# 11_Clock_1.net
KiCad netlist of a schematic drawn in Altium Designer
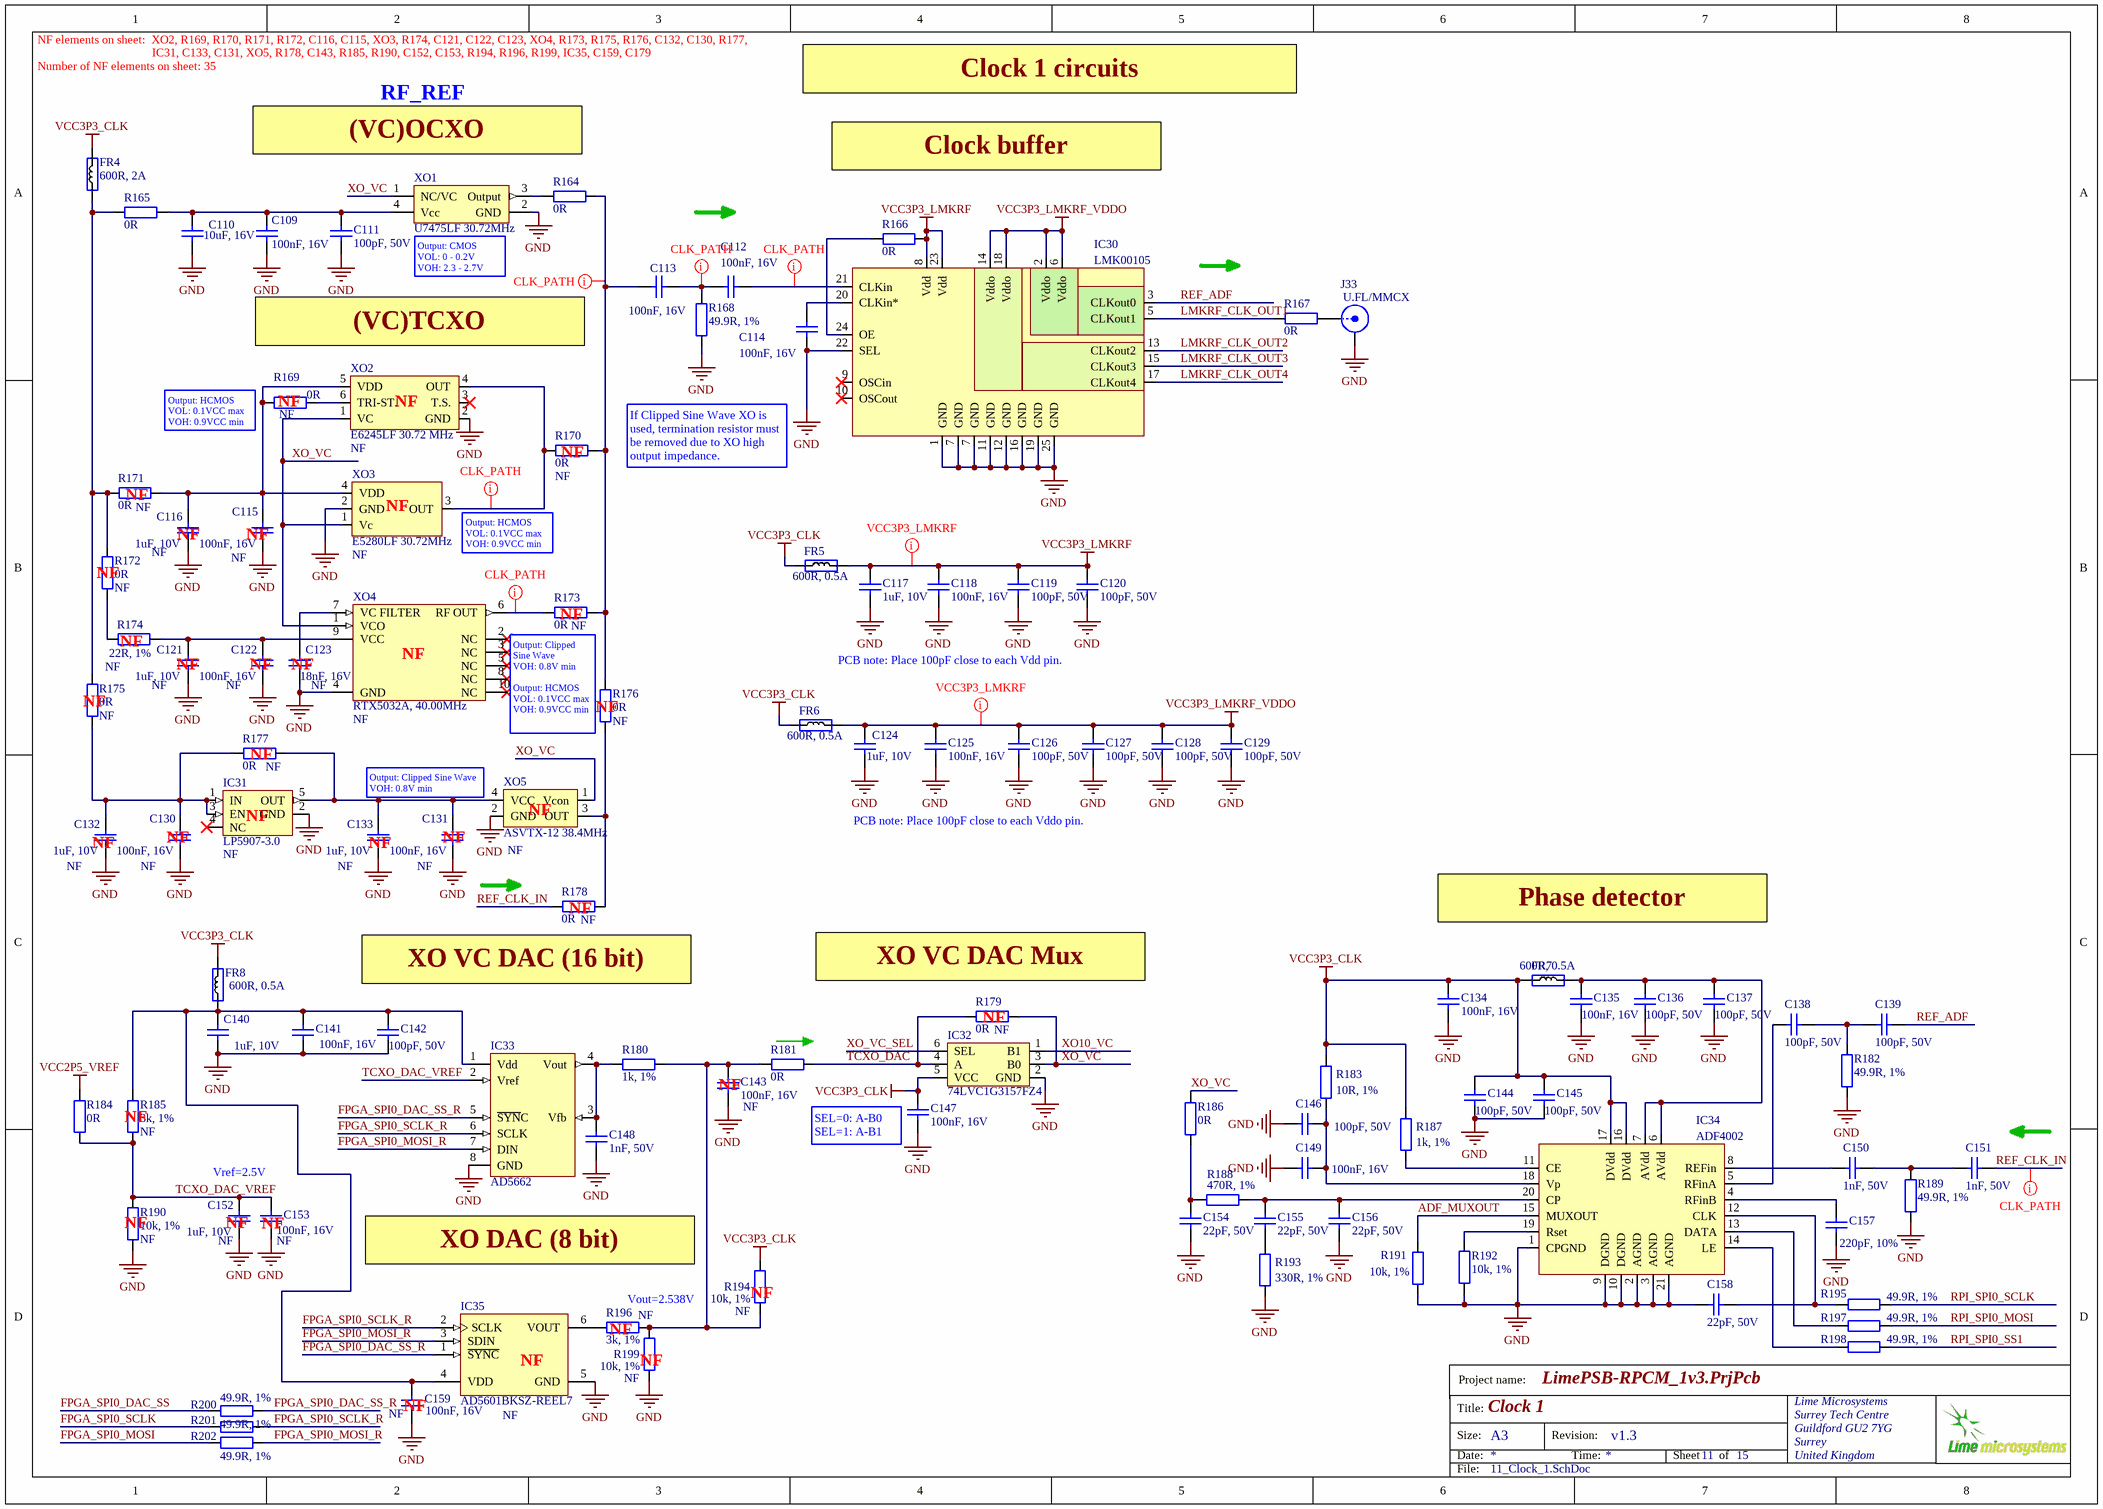
[diagram p0: 11_Clock_1.SchDoc]

(export (version "E")
  (design (tool "Eeschema 10.0.6"))
  (components
    (comp (ref "C109")
      (value "100nF, 16V")
      (footprint "CAP0402")
      (fields
        (field (name "MANUFACTURER") "Murata Electronics")
        (field (name "TOLERANCE") "10 %")
        (field (name "MANUFACTURER PART NUMBER") "GRM155R71C104KA88D")
      )
      (libsource (lib "LimeMicroAltiumLib_schLib") (part "Cap_0402"))
    )
    (comp (ref "C110")
      (value "10uF, 16V")
      (footprint "CAP0603")
      (fields (field (name "MANUFACTURER") "Yageo") (field (name "TOLERANCE") "±20%"))
      (libsource (lib "LimeMicroAltiumLib_schLib") (part "Cap_0603"))
    )
    (comp (ref "C111")
      (value "100pF, 50V")
      (footprint "CAP0402")
      (fields (field (name "TOLERANCE") "±5%") (field (name "MANUFACTURER") "Yageo"))
      (libsource (lib "LimeMicroAltiumLib_schLib") (part "Cap_0402"))
    )
    (comp (ref "C112")
      (value "100nF, 16V")
      (footprint "CAP0402")
      (fields
        (field (name "MANUFACTURER") "Murata Electronics")
        (field (name "TOLERANCE") "10 %")
        (field (name "MANUFACTURER PART NUMBER") "GRM155R71C104KA88D")
      )
      (libsource (lib "LimeMicroAltiumLib_schLib") (part "Cap_0402"))
    )
    (comp (ref "C113")
      (value "100nF, 16V")
      (footprint "CAP0402")
      (fields
        (field (name "MANUFACTURER") "Murata Electronics")
        (field (name "TOLERANCE") "10 %")
        (field (name "MANUFACTURER PART NUMBER") "GRM155R71C104KA88D")
      )
      (libsource (lib "LimeMicroAltiumLib_schLib") (part "Cap_0402"))
    )
    (comp (ref "C114")
      (value "100nF, 16V")
      (footprint "CAP0402")
      (fields
        (field (name "MANUFACTURER") "Murata Electronics")
        (field (name "TOLERANCE") "10 %")
        (field (name "MANUFACTURER PART NUMBER") "GRM155R71C104KA88D")
      )
      (libsource (lib "LimeMicroAltiumLib_schLib") (part "Cap_0402"))
    )
    (comp (ref "C115")
      (value "100nF, 16V")
      (footprint "CAP0402")
      (fields
        (field (name "ASSEMBLY INFO") "NF")
        (field (name "MANUFACTURER") "Murata Electronics")
        (field (name "TOLERANCE") "10 %")
        (field (name "MANUFACTURER PART NUMBER") "GRM155R71C104KA88D")
      )
      (libsource (lib "LimeMicroAltiumLib_schLib") (part "Cap_0402"))
    )
    (comp (ref "C116")
      (value "1uF, 10V")
      (footprint "CAP0402")
      (description "CAP CER 1UF 10V X5R 0402")
      (fields (field (name "ASSEMBLY INFO") "NF") (field (name "MANUFACTURER") "Yageo"))
      (libsource (lib "LimeMicroAltiumLib_schLib") (part "Cap_0402"))
    )
    (comp (ref "C117")
      (value "1uF, 10V")
      (footprint "CAP0402")
      (description "CAP CER 1UF 10V X5R 0402")
      (fields (field (name "MANUFACTURER") "Yageo") (field (name "TOLERANCE") "±20%"))
      (libsource (lib "LimeMicroAltiumLib_schLib") (part "Cap_0402"))
    )
    (comp (ref "C118")
      (value "100nF, 16V")
      (footprint "CAP0402")
      (fields
        (field (name "MANUFACTURER") "Murata Electronics")
        (field (name "TOLERANCE") "10 %")
        (field (name "MANUFACTURER PART NUMBER") "GRM155R71C104KA88D")
      )
      (libsource (lib "LimeMicroAltiumLib_schLib") (part "Cap_0402"))
    )
    (comp (ref "C119")
      (value "100pF, 50V")
      (footprint "CAP0402")
      (fields (field (name "MANUFACTURER") "Yageo") (field (name "TOLERANCE") "±5%"))
      (libsource (lib "LimeMicroAltiumLib_schLib") (part "Cap_0402"))
    )
    (comp (ref "C120")
      (value "100pF, 50V")
      (footprint "CAP0402")
      (fields (field (name "MANUFACTURER") "Yageo") (field (name "TOLERANCE") "±5%"))
      (libsource (lib "LimeMicroAltiumLib_schLib") (part "Cap_0402"))
    )
    (comp (ref "C121")
      (value "1uF, 10V")
      (footprint "CAP0402")
      (description "CAP CER 1UF 10V X5R 0402")
      (fields (field (name "ASSEMBLY INFO") "NF") (field (name "MANUFACTURER") "Yageo"))
      (libsource (lib "LimeMicroAltiumLib_schLib") (part "Cap_0402"))
    )
    (comp (ref "C122")
      (value "100nF, 16V")
      (footprint "CAP0402")
      (fields
        (field (name "ASSEMBLY INFO") "NF")
        (field (name "MANUFACTURER") "Murata Electronics")
        (field (name "TOLERANCE") "10 %")
        (field (name "MANUFACTURER PART NUMBER") "GRM155R71C104KA88D")
      )
      (libsource (lib "LimeMicroAltiumLib_schLib") (part "Cap_0402"))
    )
    (comp (ref "C123")
      (value "18nF, 16V")
      (footprint "CAP0402")
      (fields
        (field (name "ASSEMBLY INFO") "NF")
        (field (name "MANUFACTURER") "Yageo")
        (field (name "TOLERANCE") "±10%")
      )
      (libsource (lib "LimeMicroAltiumLib_schLib") (part "Cap_0402"))
    )
    (comp (ref "C124")
      (value "1uF, 10V")
      (footprint "CAP0402")
      (description "CAP CER 1UF 10V X5R 0402")
      (fields (field (name "MANUFACTURER") "Yageo") (field (name "TOLERANCE") "±20%"))
      (libsource (lib "LimeMicroAltiumLib_schLib") (part "Cap_0402"))
    )
    (comp (ref "C125")
      (value "100nF, 16V")
      (footprint "CAP0402")
      (fields
        (field (name "MANUFACTURER") "Murata Electronics")
        (field (name "TOLERANCE") "10 %")
        (field (name "MANUFACTURER PART NUMBER") "GRM155R71C104KA88D")
      )
      (libsource (lib "LimeMicroAltiumLib_schLib") (part "Cap_0402"))
    )
    (comp (ref "C126")
      (value "100pF, 50V")
      (footprint "CAP0402")
      (fields (field (name "MANUFACTURER") "Yageo") (field (name "TOLERANCE") "±5%"))
      (libsource (lib "LimeMicroAltiumLib_schLib") (part "Cap_0402"))
    )
    (comp (ref "C127")
      (value "100pF, 50V")
      (footprint "CAP0402")
      (fields (field (name "MANUFACTURER") "Yageo") (field (name "TOLERANCE") "±5%"))
      (libsource (lib "LimeMicroAltiumLib_schLib") (part "Cap_0402"))
    )
    (comp (ref "C128")
      (value "100pF, 50V")
      (footprint "CAP0402")
      (fields (field (name "MANUFACTURER") "Yageo") (field (name "TOLERANCE") "±5%"))
      (libsource (lib "LimeMicroAltiumLib_schLib") (part "Cap_0402"))
    )
    (comp (ref "C129")
      (value "100pF, 50V")
      (footprint "CAP0402")
      (fields (field (name "MANUFACTURER") "Yageo") (field (name "TOLERANCE") "±5%"))
      (libsource (lib "LimeMicroAltiumLib_schLib") (part "Cap_0402"))
    )
    (comp (ref "C130")
      (value "100nF, 16V")
      (footprint "CAP0402")
      (fields
        (field (name "ASSEMBLY INFO") "NF")
        (field (name "MANUFACTURER") "Murata Electronics")
        (field (name "TOLERANCE") "10 %")
        (field (name "MANUFACTURER PART NUMBER") "GRM155R71C104KA88D")
      )
      (libsource (lib "") (part "Cap_0402_1"))
    )
    (comp (ref "C131")
      (value "100nF, 16V")
      (footprint "CAP0402")
      (fields
        (field (name "ASSEMBLY INFO") "NF")
        (field (name "MANUFACTURER") "Murata Electronics")
        (field (name "TOLERANCE") "10 %")
        (field (name "MANUFACTURER PART NUMBER") "GRM155R71C104KA88D")
      )
      (libsource (lib "") (part "Cap_0402_1"))
    )
    (comp (ref "C132")
      (value "1uF, 10V")
      (footprint "CAP0402")
      (fields (field (name "ASSEMBLY INFO") "NF") (field (name "MANUFACTURER") "Yageo"))
      (libsource (lib "") (part "Cap_0402_1"))
    )
    (comp (ref "C133")
      (value "1uF, 10V")
      (footprint "CAP0402")
      (fields (field (name "ASSEMBLY INFO") "NF") (field (name "MANUFACTURER") "Yageo"))
      (libsource (lib "") (part "Cap_0402_1"))
    )
    (comp (ref "C134")
      (value "100nF, 16V")
      (footprint "CAP0402")
      (fields
        (field (name "MANUFACTURER") "Murata Electronics")
        (field (name "TOLERANCE") "10 %")
        (field (name "MANUFACTURER PART NUMBER") "GRM155R71C104KA88D")
      )
      (libsource (lib "LimeMicroAltiumLib_schLib") (part "Cap_0402"))
    )
    (comp (ref "C135")
      (value "100nF, 16V")
      (footprint "CAP0402")
      (fields
        (field (name "MANUFACTURER") "Murata Electronics")
        (field (name "TOLERANCE") "10 %")
        (field (name "MANUFACTURER PART NUMBER") "GRM155R71C104KA88D")
      )
      (libsource (lib "LimeMicroAltiumLib_schLib") (part "Cap_0402"))
    )
    (comp (ref "C136")
      (value "100pF, 50V")
      (footprint "CAP0402")
      (fields (field (name "MANUFACTURER") "Yageo") (field (name "TOLERANCE") "±5%"))
      (libsource (lib "LimeMicroAltiumLib_schLib") (part "Cap_0402"))
    )
    (comp (ref "C137")
      (value "100pF, 50V")
      (footprint "CAP0402")
      (fields (field (name "MANUFACTURER") "Yageo") (field (name "TOLERANCE") "±5%"))
      (libsource (lib "LimeMicroAltiumLib_schLib") (part "Cap_0402"))
    )
    (comp (ref "C138")
      (value "100pF, 50V")
      (footprint "CAP0402")
      (fields (field (name "MANUFACTURER") "Yageo") (field (name "TOLERANCE") "±5%"))
      (libsource (lib "LimeMicroAltiumLib_schLib") (part "Cap_0402"))
    )
    (comp (ref "C139")
      (value "100pF, 50V")
      (footprint "CAP0402")
      (fields (field (name "MANUFACTURER") "Yageo") (field (name "TOLERANCE") "±5%"))
      (libsource (lib "LimeMicroAltiumLib_schLib") (part "Cap_0402"))
    )
    (comp (ref "C140")
      (value "1uF, 10V")
      (footprint "CAP0402")
      (description "CAP CER 1UF 10V X5R 0402")
      (fields (field (name "MANUFACTURER") "Yageo") (field (name "TOLERANCE") "±20%"))
      (libsource (lib "LimeMicroAltiumLib_schLib") (part "Cap_0402"))
    )
    (comp (ref "C141")
      (value "100nF, 16V")
      (footprint "CAP0402")
      (fields
        (field (name "TOLERANCE") "10 %")
        (field (name "MANUFACTURER") "Murata Electronics")
        (field (name "MANUFACTURER PART NUMBER") "GRM155R71C104KA88D")
      )
      (libsource (lib "LimeFPGAboard_schLib") (part "Cap_0603"))
    )
    (comp (ref "C142")
      (value "100pF, 50V")
      (footprint "CAP0402")
      (fields (field (name "MANUFACTURER") "Yageo") (field (name "TOLERANCE") "±5%"))
      (libsource (lib "LimeMicroAltiumLib_schLib") (part "Cap_0402"))
    )
    (comp (ref "C143")
      (value "100nF, 16V")
      (footprint "CAP0402")
      (fields
        (field (name "ASSEMBLY INFO") "NF")
        (field (name "MANUFACTURER") "Murata Electronics")
        (field (name "TOLERANCE") "10 %")
        (field (name "MANUFACTURER PART NUMBER") "GRM155R71C104KA88D")
      )
      (libsource (lib "LimeMicroAltiumLib_schLib") (part "Cap_0402"))
    )
    (comp (ref "C144")
      (value "100pF, 50V")
      (footprint "CAP0402")
      (fields (field (name "MANUFACTURER") "Yageo") (field (name "TOLERANCE") "±5%"))
      (libsource (lib "LimeMicroAltiumLib_schLib") (part "Cap_0402"))
    )
    (comp (ref "C145")
      (value "100pF, 50V")
      (footprint "CAP0402")
      (fields (field (name "MANUFACTURER") "Yageo") (field (name "TOLERANCE") "±5%"))
      (libsource (lib "LimeMicroAltiumLib_schLib") (part "Cap_0402"))
    )
    (comp (ref "C146")
      (value "100pF, 50V")
      (footprint "CAP0402")
      (fields (field (name "MANUFACTURER") "Yageo") (field (name "TOLERANCE") "±5%"))
      (libsource (lib "LimeMicroAltiumLib_schLib") (part "Cap_0402"))
    )
    (comp (ref "C147")
      (value "100nF, 16V")
      (footprint "CAP0402")
      (fields
        (field (name "MANUFACTURER") "Murata Electronics")
        (field (name "TOLERANCE") "10 %")
        (field (name "MANUFACTURER PART NUMBER") "GRM155R71C104KA88D")
      )
      (libsource (lib "LimeMicroAltiumLib_schLib") (part "Cap_0402"))
    )
    (comp (ref "C148")
      (value "1nF, 50V")
      (footprint "CAP0402")
      (fields
        (field (name "TOLERANCE") "±10%")
        (field (name "MANUFACTURER") "Murata Electronics North America")
      )
      (libsource (lib "LimeMicroAltiumLib_schLib") (part "Cap_0402"))
    )
    (comp (ref "C149")
      (value "100nF, 16V")
      (footprint "CAP0402")
      (fields
        (field (name "MANUFACTURER") "Murata Electronics")
        (field (name "TOLERANCE") "10 %")
        (field (name "MANUFACTURER PART NUMBER") "GRM155R71C104KA88D")
      )
      (libsource (lib "LimeMicroAltiumLib_schLib") (part "Cap_0402"))
    )
    (comp (ref "C150")
      (value "1nF, 50V")
      (footprint "CAP0402")
      (fields
        (field (name "TOLERANCE") "±10%")
        (field (name "MANUFACTURER") "Murata Electronics North America")
      )
      (libsource (lib "LimeMicroAltiumLib_schLib") (part "Cap_0402"))
    )
    (comp (ref "C151")
      (value "1nF, 50V")
      (footprint "CAP0402")
      (fields
        (field (name "TOLERANCE") "±10%")
        (field (name "MANUFACTURER") "Murata Electronics North America")
      )
      (libsource (lib "LimeMicroAltiumLib_schLib") (part "Cap_0402"))
    )
    (comp (ref "C152")
      (value "1uF, 10V")
      (footprint "CAP0402")
      (description "CAP CER 1UF 10V X5R 0402")
      (fields
        (field (name "ASSEMBLY INFO") "NF")
        (field (name "MANUFACTURER") "Yageo")
        (field (name "TOLERANCE") "±20%")
      )
      (libsource (lib "LimeMicroAltiumLib_schLib") (part "Cap_0402"))
    )
    (comp (ref "C153")
      (value "100nF, 16V")
      (footprint "CAP0402")
      (fields
        (field (name "TOLERANCE") "10 %")
        (field (name "MANUFACTURER") "Murata Electronics")
        (field (name "MANUFACTURER PART NUMBER") "GRM155R71C104KA88D")
        (field (name "ASSEMBLY INFO") "NF")
      )
      (libsource (lib "LimeFPGAboard_schLib") (part "Cap_0603"))
    )
    (comp (ref "C154")
      (value "22pF, 50V")
      (footprint "CAP0402")
      (fields (field (name "TOLERANCE") "±5%") (field (name "MANUFACTURER") "Yageo"))
      (libsource (lib "LimeMicroAltiumLib_schLib") (part "Cap_0402"))
    )
    (comp (ref "C155")
      (value "22pF, 50V")
      (footprint "CAP0402")
      (fields (field (name "TOLERANCE") "±5%") (field (name "MANUFACTURER") "Yageo"))
      (libsource (lib "LimeMicroAltiumLib_schLib") (part "Cap_0402"))
    )
    (comp (ref "C156")
      (value "22pF, 50V")
      (footprint "CAP0402")
      (fields (field (name "TOLERANCE") "±5%") (field (name "MANUFACTURER") "Yageo"))
      (libsource (lib "LimeMicroAltiumLib_schLib") (part "Cap_0402"))
    )
    (comp (ref "C157")
      (value "220pF, 10%")
      (footprint "CAP0402")
      (fields (field (name "MANUFACTURER") "Yageo") (field (name "TOLERANCE") "±10%"))
      (libsource (lib "LimeMicroAltiumLib_schLib") (part "Cap_0402"))
    )
    (comp (ref "C158")
      (value "22pF, 50V")
      (footprint "CAP0402")
      (fields (field (name "TOLERANCE") "±5%") (field (name "MANUFACTURER") "Yageo"))
      (libsource (lib "LimeMicroAltiumLib_schLib") (part "Cap_0402"))
    )
    (comp (ref "C159")
      (value "100nF, 16V")
      (footprint "CAP0402")
      (fields
        (field (name "TOLERANCE") "10 %")
        (field (name "MANUFACTURER") "Murata Electronics")
        (field (name "MANUFACTURER PART NUMBER") "GRM155R71C104KA88D")
        (field (name "ASSEMBLY INFO") "NF")
      )
      (libsource (lib "LimeFPGAboard_schLib") (part "Cap_0603"))
    )
    (comp (ref "FR4")
      (value "600R, 2A")
      (footprint "RES0805")
      (fields (field (name "MANUFACTURER") "TDK Corporation"))
      (libsource (lib "LimeFPGAboard_schLib") (part "Ferrite"))
    )
    (comp (ref "FR5")
      (value "600R, 0.5A")
      (footprint "RES0402")
      (fields (field (name "MANUFACTURER") "Murata") (field (name "TOLERANCE") "25%"))
      (libsource (lib "LimeMicroAltiumLib_schLib") (part "Ferrite"))
    )
    (comp (ref "FR6")
      (value "600R, 0.5A")
      (footprint "RES0402")
      (fields (field (name "MANUFACTURER") "Murata") (field (name "TOLERANCE") "25%"))
      (libsource (lib "LimeMicroAltiumLib_schLib") (part "Ferrite"))
    )
    (comp (ref "FR7")
      (value "600R, 0.5A")
      (footprint "RES0402")
      (fields (field (name "MANUFACTURER") "Murata") (field (name "TOLERANCE") "25%"))
      (libsource (lib "LimeMicroAltiumLib_schLib") (part "Ferrite"))
    )
    (comp (ref "FR8")
      (value "600R, 0.5A")
      (footprint "RES0402")
      (fields (field (name "MANUFACTURER") "Murata") (field (name "TOLERANCE") "25%"))
      (libsource (lib "LimeMicroAltiumLib_schLib") (part "Ferrite"))
    )
    (comp (ref "IC30")
      (value "LMK00105")
      (footprint "LMK00105SQ")
      (fields (field (name "MANUFACTURER") "Texas Instruments"))
      (libsource (lib "LimeMicroAltiumLib_schLib") (part "LMK00105"))
    )
    (comp (ref "IC31")
      (value "LP5907-3.0")
      (footprint "SOT23-5")
      (fields (field (name "MANUFACTURER") "Texas Instruments") (field (name "ASSEMBLY INFO") "NF"))
      (libsource (lib "LimeMicroAltiumLib_schLib_r01") (part "LP5907"))
    )
    (comp (ref "IC32")
      (value "74LVC1G3157FZ4")
      (footprint "74LVC1G3157FZ4_SPDT_SW_DFN1410-6")
      (fields (field (name "MANUFACTURER") "Diodes"))
      (libsource (lib "LimeMicroAltiumLib_schLib_r04") (part "74LVC1G3157FZ4_SPDT_SW"))
    )
    (comp (ref "IC33")
      (value "AD5662")
      (footprint "AD5662_SOT23-8")
      (fields (field (name "MANUFACTURER") "Analog Devices Inc."))
      (libsource (lib "LimeMicroAltiumLib_schLib") (part "AD5662"))
    )
    (comp (ref "IC34")
      (value "ADF4002")
      (footprint "ADF4002")
      (fields (field (name "MANUFACTURER") "Analog Devices Inc"))
      (libsource (lib "LimeMicroAltiumLib_schLib") (part "ADF4002"))
    )
    (comp (ref "IC35")
      (value "AD5601BKSZ-REEL7")
      (footprint "AD5601_SOT23-6")
      (fields
        (field (name "GENERIC PART NUMBER") "AD5601")
        (field (name "MANUFACTURER") "Analog Devices")
        (field (name "ASSEMBLY INFO") "NF")
      )
      (libsource (lib "LimeMicroAltiumLib_schLib") (part "AD5601BKSZ-REEL7"))
    )
    (comp (ref "J33")
      (value "U.FL/MMCX")
      (footprint "MMCX_UFL_conn_u")
      (description "CONN UMC RCPT STR 50 OHM SMD")
      (fields (field (name "MANUFACTURER") "Molex, LLC"))
      (libsource (lib "LimeMicroAltiumLib_schLib") (part "RF_IF_connector"))
    )
    (comp (ref "R164")
      (value "0R")
      (footprint "RES0402_v2")
      (fields (field (name "MANUFACTURER") "Yageo") (field (name "TOLERANCE") "Jumper"))
      (libsource (lib "LimeMicroAltiumLib_schLib") (part "Res_0402"))
    )
    (comp (ref "R165")
      (value "0R")
      (footprint "RES0402")
      (fields (field (name "MANUFACTURER") "Yageo") (field (name "TOLERANCE") "Jumper"))
      (libsource (lib "LimeMicroAltiumLib_schLib") (part "Res_0402"))
    )
    (comp (ref "R166")
      (value "0R")
      (footprint "RES0402")
      (fields (field (name "MANUFACTURER") "Yageo") (field (name "TOLERANCE") "Jumper"))
      (libsource (lib "LimeMicroAltiumLib_schLib") (part "Res_0402"))
    )
    (comp (ref "R167")
      (value "0R")
      (footprint "RES0402")
      (fields (field (name "MANUFACTURER") "Yageo") (field (name "TOLERANCE") "Jumper"))
      (libsource (lib "") (part "Res_0402_1"))
    )
    (comp (ref "R168")
      (value "49.9R, 1%")
      (footprint "RES0402")
      (fields
        (field (name "TOLERANCE") "±1%")
        (field (name "MANUFACTURER") "Samsung Electro-Mechanics America, Inc.")
      )
      (libsource (lib "LimeMicroAltiumLib_schLib") (part "Res_0402"))
    )
    (comp (ref "R169")
      (value "0R")
      (footprint "RES0402")
      (fields
        (field (name "ASSEMBLY INFO") "NF")
        (field (name "MANUFACTURER") "Yageo")
        (field (name "TOLERANCE") "Jumper")
      )
      (libsource (lib "LimeMicroAltiumLib_schLib") (part "Res_0402"))
    )
    (comp (ref "R170")
      (value "0R")
      (footprint "RES0402_v2")
      (fields
        (field (name "ASSEMBLY INFO") "NF")
        (field (name "MANUFACTURER") "Yageo")
        (field (name "TOLERANCE") "Jumper")
      )
      (libsource (lib "LimeMicroAltiumLib_schLib") (part "Res_0402"))
    )
    (comp (ref "R171")
      (value "0R")
      (footprint "RES0402")
      (fields
        (field (name "MANUFACTURER") "Yageo")
        (field (name "TOLERANCE") "Jumper")
        (field (name "ASSEMBLY INFO") "NF")
      )
      (libsource (lib "LimeMicroAltiumLib_schLib") (part "Res_0402"))
    )
    (comp (ref "R172")
      (value "0R")
      (footprint "RES0402")
      (fields
        (field (name "ASSEMBLY INFO") "NF")
        (field (name "MANUFACTURER") "Yageo")
        (field (name "TOLERANCE") "Jumper")
      )
      (libsource (lib "LimeMicroAltiumLib_schLib") (part "Res_0402"))
    )
    (comp (ref "R173")
      (value "0R")
      (footprint "RES0402_v2")
      (fields
        (field (name "ASSEMBLY INFO") "NF")
        (field (name "MANUFACTURER") "Yageo")
        (field (name "TOLERANCE") "Jumper")
      )
      (libsource (lib "LimeMicroAltiumLib_schLib") (part "Res_0402"))
    )
    (comp (ref "R174")
      (value "22R, 1%")
      (footprint "RES0402")
      (fields
        (field (name "TOLERANCE") "±1%")
        (field (name "MANUFACTURER") "Yageo")
        (field (name "ASSEMBLY INFO") "NF")
      )
      (libsource (lib "LimeFPGAboard_schLib") (part "Res_0402"))
    )
    (comp (ref "R175")
      (value "0R")
      (footprint "RES0402")
      (fields
        (field (name "MANUFACTURER") "Yageo")
        (field (name "TOLERANCE") "Jumper")
        (field (name "ASSEMBLY INFO") "NF")
      )
      (libsource (lib "") (part "Res_0402_1"))
    )
    (comp (ref "R176")
      (value "0R")
      (footprint "RES0402_v2")
      (fields
        (field (name "ASSEMBLY INFO") "NF")
        (field (name "MANUFACTURER") "Yageo")
        (field (name "TOLERANCE") "Jumper")
      )
      (libsource (lib "") (part "Res_0402_1"))
    )
    (comp (ref "R177")
      (value "0R")
      (footprint "RES0402")
      (fields
        (field (name "MANUFACTURER") "Yageo")
        (field (name "TOLERANCE") "Jumper")
        (field (name "ASSEMBLY INFO") "NF")
      )
      (libsource (lib "") (part "Res_0402_1"))
    )
    (comp (ref "R178")
      (value "0R")
      (footprint "RES0402_v2")
      (fields
        (field (name "ASSEMBLY INFO") "NF")
        (field (name "MANUFACTURER") "Yageo")
        (field (name "TOLERANCE") "Jumper")
      )
      (libsource (lib "LimeMicroAltiumLib_schLib") (part "Res_0402"))
    )
    (comp (ref "R179")
      (value "0R")
      (footprint "RES0402_v2")
      (fields
        (field (name "ASSEMBLY INFO") "NF")
        (field (name "MANUFACTURER") "Yageo")
        (field (name "TOLERANCE") "Jumper")
      )
      (libsource (lib "LimeMicroAltiumLib_schLib") (part "Res_0402"))
    )
    (comp (ref "R180")
      (value "1k, 1%")
      (footprint "RES0402")
      (fields (field (name "MANUFACTURER") "Stackpole Electronics Inc") (field (name "TOLERANCE") "±1%"))
      (libsource (lib "LimeMicroAltiumLib_schLib") (part "Res_0402"))
    )
    (comp (ref "R181")
      (value "0R")
      (footprint "RES0402")
      (fields (field (name "MANUFACTURER") "Yageo") (field (name "TOLERANCE") "Jumper"))
      (libsource (lib "LimeMicroAltiumLib_schLib") (part "Res_0402"))
    )
    (comp (ref "R182")
      (value "49.9R, 1%")
      (footprint "RES0402")
      (fields
        (field (name "TOLERANCE") "±1%")
        (field (name "MANUFACTURER") "Samsung Electro-Mechanics America, Inc.")
      )
      (libsource (lib "LimeMicroAltiumLib_schLib") (part "Res_0402"))
    )
    (comp (ref "R183")
      (value "10R, 1%")
      (footprint "RES0402")
      (fields (field (name "MANUFACTURER") "Stackpole Electronics") (field (name "TOLERANCE") "1%"))
      (libsource (lib "LimeMicroAltiumLib_schLib") (part "Res_0402"))
    )
    (comp (ref "R184")
      (value "0R")
      (footprint "RES0402_v2")
      (fields (field (name "MANUFACTURER") "Yageo") (field (name "TOLERANCE") "Jumper"))
      (libsource (lib "LimeMicroAltiumLib_schLib") (part "Res_0402"))
    )
    (comp (ref "R185")
      (value "3k, 1%")
      (footprint "RES0402")
      (fields
        (field (name "ASSEMBLY INFO") "NF")
        (field (name "TOLERANCE") "±1%")
        (field (name "MANUFACTURER") "Vishay Dale")
      )
      (libsource (lib "LimeMicroAltiumLib_schLib") (part "Res_0402"))
    )
    (comp (ref "R186")
      (value "0R")
      (footprint "RES0402")
      (fields (field (name "MANUFACTURER") "Yageo") (field (name "TOLERANCE") "Jumper"))
      (libsource (lib "LimeMicroAltiumLib_schLib") (part "Res_0402"))
    )
    (comp (ref "R187")
      (value "1k, 1%")
      (footprint "RES0402")
      (fields (field (name "MANUFACTURER") "Stackpole Electronics Inc") (field (name "TOLERANCE") "±1%"))
      (libsource (lib "LimeMicroAltiumLib_schLib") (part "Res_0402"))
    )
    (comp (ref "R188")
      (value "470R, 1%")
      (footprint "RES0402")
      (fields (field (name "TOLERANCE") "1%") (field (name "MANUFACTURER") "Yageo"))
      (libsource (lib "") (part "Res_0402_1"))
    )
    (comp (ref "R189")
      (value "49.9R, 1%")
      (footprint "RES0402")
      (fields
        (field (name "TOLERANCE") "±1%")
        (field (name "MANUFACTURER") "Samsung Electro-Mechanics America, Inc.")
      )
      (libsource (lib "LimeMicroAltiumLib_schLib") (part "Res_0402"))
    )
    (comp (ref "R190")
      (value "10k, 1%")
      (footprint "RES0402")
      (fields
        (field (name "ASSEMBLY INFO") "NF")
        (field (name "MANUFACTURER") "Yageo")
        (field (name "TOLERANCE") "±1%")
      )
      (libsource (lib "LimeMicroAltiumLib_schLib") (part "Res_0402"))
    )
    (comp (ref "R191")
      (value "10k, 1%")
      (footprint "RES0402")
      (fields (field (name "MANUFACTURER") "Yageo") (field (name "TOLERANCE") "±1%"))
      (libsource (lib "LimeMicroAltiumLib_schLib") (part "Res_0402"))
    )
    (comp (ref "R192")
      (value "10k, 1%")
      (footprint "RES0402")
      (fields (field (name "MANUFACTURER") "Yageo") (field (name "TOLERANCE") "±1%"))
      (libsource (lib "LimeMicroAltiumLib_schLib") (part "Res_0402"))
    )
    (comp (ref "R193")
      (value "330R, 1%")
      (footprint "RES0402")
      (fields (field (name "MANUFACTURER") "Yageo") (field (name "TOLERANCE") "1%"))
      (libsource (lib "LimeMicroAltiumLib_schLib") (part "Res_0402"))
    )
    (comp (ref "R194")
      (value "10k, 1%")
      (footprint "RES0402")
      (fields
        (field (name "ASSEMBLY INFO") "NF")
        (field (name "MANUFACTURER") "Yageo")
        (field (name "TOLERANCE") "±1%")
      )
      (libsource (lib "LimeMicroAltiumLib_schLib") (part "Res_0402"))
    )
    (comp (ref "R195")
      (value "49.9R, 1%")
      (footprint "RES0402")
      (fields
        (field (name "TOLERANCE") "±1%")
        (field (name "MANUFACTURER") "Samsung Electro-Mechanics America, Inc.")
      )
      (libsource (lib "LimeMicroAltiumLib_schLib") (part "Res_0402"))
    )
    (comp (ref "R196")
      (value "3k, 1%")
      (footprint "RES0402")
      (fields
        (field (name "ASSEMBLY INFO") "NF")
        (field (name "TOLERANCE") "±1%")
        (field (name "MANUFACTURER") "Vishay Dale")
      )
      (libsource (lib "LimeMicroAltiumLib_schLib") (part "Res_0402"))
    )
    (comp (ref "R197")
      (value "49.9R, 1%")
      (footprint "RES0402")
      (fields
        (field (name "TOLERANCE") "±1%")
        (field (name "MANUFACTURER") "Samsung Electro-Mechanics America, Inc.")
      )
      (libsource (lib "LimeMicroAltiumLib_schLib") (part "Res_0402"))
    )
    (comp (ref "R198")
      (value "49.9R, 1%")
      (footprint "RES0402")
      (fields
        (field (name "TOLERANCE") "±1%")
        (field (name "MANUFACTURER") "Samsung Electro-Mechanics America, Inc.")
      )
      (libsource (lib "LimeMicroAltiumLib_schLib") (part "Res_0402"))
    )
    (comp (ref "R199")
      (value "10k, 1%")
      (footprint "RES0402")
      (fields
        (field (name "ASSEMBLY INFO") "NF")
        (field (name "MANUFACTURER") "Yageo")
        (field (name "TOLERANCE") "±1%")
      )
      (libsource (lib "LimeMicroAltiumLib_schLib") (part "Res_0402"))
    )
    (comp (ref "R200")
      (value "49.9R, 1%")
      (footprint "RES0402")
      (fields
        (field (name "TOLERANCE") "±1%")
        (field (name "MANUFACTURER") "Samsung Electro-Mechanics America, Inc.")
      )
      (libsource (lib "LimeMicroAltiumLib_schLib") (part "Res_0402"))
    )
    (comp (ref "R201")
      (value "49.9R, 1%")
      (footprint "RES0402")
      (fields
        (field (name "TOLERANCE") "±1%")
        (field (name "MANUFACTURER") "Samsung Electro-Mechanics America, Inc.")
      )
      (libsource (lib "LimeMicroAltiumLib_schLib") (part "Res_0402"))
    )
    (comp (ref "R202")
      (value "49.9R, 1%")
      (footprint "RES0402")
      (fields
        (field (name "TOLERANCE") "±1%")
        (field (name "MANUFACTURER") "Samsung Electro-Mechanics America, Inc.")
      )
      (libsource (lib "LimeMicroAltiumLib_schLib") (part "Res_0402"))
    )
    (comp (ref "XO1")
      (value "U7475LF 30.72MHz")
      (footprint "AOCJYR-10.000MHz")
      (fields (field (name "MANUFACTURER") "Rakon"))
      (libsource (lib "LimeMicroAltiumLib_schLib") (part "AOCJYR-10.000MHz"))
    )
    (comp (ref "XO2")
      (value "E6245LF 30.72 MHz")
      (footprint "RAKON_RPT7050A")
      (fields (field (name "ASSEMBLY INFO") "NF") (field (name "MANUFACTURER") "Rakon"))
      (libsource (lib "LimeMicroAltiumLib_schLib") (part "RPT7050A"))
    )
    (comp (ref "XO3")
      (value "E5280LF 30.72MHz")
      (footprint "RAKON_TXCO")
      (fields (field (name "ASSEMBLY INFO") "NF") (field (name "MANUFACTURER") "Rakon"))
      (libsource (lib "LimeMicroAltiumLib_schLib") (part "TXCO"))
    )
    (comp (ref "XO4")
      (value "RTX5032A, 40.00MHz")
      (footprint "RAKON_RTX5032A")
      (fields (field (name "ASSEMBLY INFO") "NF") (field (name "MANUFACTURER") "Rakon"))
      (libsource (lib "LimeMicroAltiumLib_schLib") (part "Rakon_RTX5032A"))
    )
    (comp (ref "XO5")
      (value "ASVTX-12 38.4MHz")
      (footprint "CRYSTAL_4-LCC_2P5x2P0")
      (description "Oscillator Crystal")
      (fields (field (name "MANUFACTURER") "Abracon") (field (name "ASSEMBLY INFO") "NF"))
      (libsource (lib "LimeMicroAltiumLib_schLib_r01") (part "ASVTX-12-A-38.400MHZ-H10-T_CRYSTAL"))
    )
  )
  (nets
    (net (code "2") (name "/ADF_MUXOUT") (class "Default")
      (node (ref "IC34") (pin "15") (pinfunction "MUXOUT_15") (pintype "passive"))
      (node (ref "R191") (pin "1") (pinfunction "1_1") (pintype "passive"))
    )
    (net (code "3") (name "/FPGA_SPI0_DAC_SS") (class "Default")
      (node (ref "R200") (pin "2") (pinfunction "2_2") (pintype "passive"))
    )
    (net (code "4") (name "/FPGA_SPI0_DAC_SS_R") (class "Default")
      (node (ref "IC33") (pin "5") (pinfunction "~{SYN}C_5") (pintype "input"))
      (node (ref "IC35") (pin "1") (pinfunction "~{SYNC}_1") (pintype "input"))
      (node (ref "R200") (pin "1") (pinfunction "1_1") (pintype "passive"))
    )
    (net (code "5") (name "/FPGA_SPI0_MOSI") (class "Default")
      (node (ref "R202") (pin "2") (pinfunction "2_2") (pintype "passive"))
    )
    (net (code "6") (name "/FPGA_SPI0_MOSI_R") (class "Default")
      (node (ref "IC33") (pin "7") (pinfunction "DIN_7") (pintype "input"))
      (node (ref "IC35") (pin "3") (pinfunction "SDIN_3") (pintype "input"))
      (node (ref "R202") (pin "1") (pinfunction "1_1") (pintype "passive"))
    )
    (net (code "7") (name "/FPGA_SPI0_SCLK") (class "Default")
      (node (ref "R201") (pin "2") (pinfunction "2_2") (pintype "passive"))
    )
    (net (code "8") (name "/FPGA_SPI0_SCLK_R") (class "Default")
      (node (ref "IC33") (pin "6") (pinfunction "SCLK_6") (pintype "input"))
      (node (ref "IC35") (pin "2") (pinfunction "SCLK_2") (pintype "input"))
      (node (ref "R201") (pin "1") (pinfunction "1_1") (pintype "passive"))
    )
    (net (code "9") (name "/LMKRF_CLK_OUT1") (class "Default")
      (node (ref "IC30") (pin "5") (pinfunction "CLKout1_5") (pintype "passive"))
      (node (ref "R167") (pin "2") (pinfunction "2_2") (pintype "passive"))
    )
    (net (code "10") (name "/LMKRF_CLK_OUT2") (class "Default")
      (node (ref "IC30") (pin "13") (pinfunction "CLKout2_13") (pintype "passive"))
    )
    (net (code "11") (name "/LMKRF_CLK_OUT3") (class "Default")
      (node (ref "IC30") (pin "15") (pinfunction "CLKout3_15") (pintype "passive"))
    )
    (net (code "12") (name "/LMKRF_CLK_OUT4") (class "Default")
      (node (ref "IC30") (pin "17") (pinfunction "CLKout4_17") (pintype "passive"))
    )
    (net (code "13") (name "/REF_ADF") (class "Default")
      (node (ref "C139") (pin "2") (pinfunction "2_2") (pintype "passive"))
      (node (ref "IC30") (pin "3") (pinfunction "CLKout0_3") (pintype "passive"))
    )
    (net (code "14") (name "/REF_CLK_IN") (class "Default")
      (node (ref "C151") (pin "2") (pinfunction "2_2") (pintype "passive"))
      (node (ref "R178") (pin "2") (pinfunction "2_2") (pintype "passive"))
    )
    (net (code "15") (name "/RPI_SPI0_MOSI") (class "Default")
      (node (ref "R197") (pin "1") (pinfunction "1_1") (pintype "passive"))
    )
    (net (code "16") (name "/RPI_SPI0_SCLK") (class "Default")
      (node (ref "R195") (pin "1") (pinfunction "1_1") (pintype "passive"))
    )
    (net (code "17") (name "/RPI_SPI0_SS1") (class "Default")
      (node (ref "R198") (pin "1") (pinfunction "1_1") (pintype "passive"))
    )
    (net (code "18") (name "/TCXO_DAC") (class "Default")
      (node (ref "IC32") (pin "4") (pinfunction "A_4") (pintype "passive"))
      (node (ref "R179") (pin "2") (pinfunction "2_2") (pintype "passive"))
      (node (ref "R181") (pin "1") (pinfunction "1_1") (pintype "passive"))
    )
    (net (code "19") (name "/TCXO_DAC_VREF") (class "Default")
      (node (ref "C152") (pin "2") (pinfunction "2_2") (pintype "passive"))
      (node (ref "C153") (pin "1") (pinfunction "1_1") (pintype "passive"))
      (node (ref "IC33") (pin "2") (pinfunction "Vref_2") (pintype "input"))
      (node (ref "R184") (pin "1") (pinfunction "1_1") (pintype "passive"))
      (node (ref "R185") (pin "1") (pinfunction "1_1") (pintype "passive"))
      (node (ref "R190") (pin "1") (pinfunction "1_1") (pintype "passive"))
    )
    (net (code "20") (name "/XO10_VC") (class "Default")
      (node (ref "IC32") (pin "1") (pinfunction "B1_1") (pintype "passive"))
    )
    (net (code "21") (name "/XO_VC") (class "Default")
      (node (ref "IC32") (pin "3") (pinfunction "B0_3") (pintype "passive"))
      (node (ref "R179") (pin "1") (pinfunction "1_1") (pintype "passive"))
      (node (ref "R186") (pin "2") (pinfunction "2_2") (pintype "passive"))
      (node (ref "XO1") (pin "1") (pinfunction "NC/VC_1") (pintype "passive"))
      (node (ref "XO2") (pin "1") (pinfunction "VC_1") (pintype "passive"))
      (node (ref "XO3") (pin "1") (pinfunction "Vc_1") (pintype "passive"))
      (node (ref "XO4") (pin "1") (pinfunction "VCO_1") (pintype "input"))
      (node (ref "XO5") (pin "1") (pinfunction "Vcon_1") (pintype "passive"))
    )
    (net (code "22") (name "/XO_VC_SEL") (class "Default")
      (node (ref "IC32") (pin "6") (pinfunction "SEL_6") (pintype "passive"))
    )
    (net (code "23") (name "GND") (class "Default")
      (node (ref "C109") (pin "1") (pinfunction "1_1") (pintype "passive"))
      (node (ref "C110") (pin "1") (pinfunction "1_1") (pintype "passive"))
      (node (ref "C111") (pin "2") (pinfunction "2_2") (pintype "passive"))
      (node (ref "C114") (pin "1") (pinfunction "1_1") (pintype "passive"))
      (node (ref "C115") (pin "1") (pinfunction "1_1") (pintype "passive"))
      (node (ref "C116") (pin "1") (pinfunction "1_1") (pintype "passive"))
      (node (ref "C117") (pin "1") (pinfunction "1_1") (pintype "passive"))
      (node (ref "C118") (pin "1") (pinfunction "1_1") (pintype "passive"))
      (node (ref "C119") (pin "1") (pinfunction "1_1") (pintype "passive"))
      (node (ref "C120") (pin "1") (pinfunction "1_1") (pintype "passive"))
      (node (ref "C121") (pin "1") (pinfunction "1_1") (pintype "passive"))
      (node (ref "C122") (pin "1") (pinfunction "1_1") (pintype "passive"))
      (node (ref "C123") (pin "1") (pinfunction "1_1") (pintype "passive"))
      (node (ref "C124") (pin "1") (pinfunction "1_1") (pintype "passive"))
      (node (ref "C125") (pin "1") (pinfunction "1_1") (pintype "passive"))
      (node (ref "C126") (pin "1") (pinfunction "1_1") (pintype "passive"))
      (node (ref "C127") (pin "1") (pinfunction "1_1") (pintype "passive"))
      (node (ref "C128") (pin "1") (pinfunction "1_1") (pintype "passive"))
      (node (ref "C129") (pin "1") (pinfunction "1_1") (pintype "passive"))
      (node (ref "C130") (pin "1") (pinfunction "1_1") (pintype "passive"))
      (node (ref "C131") (pin "1") (pinfunction "1_1") (pintype "passive"))
      (node (ref "C132") (pin "1") (pinfunction "1_1") (pintype "passive"))
      (node (ref "C133") (pin "1") (pinfunction "1_1") (pintype "passive"))
      (node (ref "C134") (pin "1") (pinfunction "1_1") (pintype "passive"))
      (node (ref "C135") (pin "1") (pinfunction "1_1") (pintype "passive"))
      (node (ref "C136") (pin "2") (pinfunction "2_2") (pintype "passive"))
      (node (ref "C137") (pin "2") (pinfunction "2_2") (pintype "passive"))
      (node (ref "C140") (pin "1") (pinfunction "1_1") (pintype "passive"))
      (node (ref "C141") (pin "2") (pinfunction "2_2") (pintype "passive"))
      (node (ref "C142") (pin "2") (pinfunction "2_2") (pintype "passive"))
      (node (ref "C143") (pin "1") (pinfunction "1_1") (pintype "passive"))
      (node (ref "C144") (pin "2") (pinfunction "2_2") (pintype "passive"))
      (node (ref "C145") (pin "2") (pinfunction "2_2") (pintype "passive"))
      (node (ref "C146") (pin "1") (pinfunction "1_1") (pintype "passive"))
      (node (ref "C147") (pin "1") (pinfunction "1_1") (pintype "passive"))
      (node (ref "C148") (pin "2") (pinfunction "2_2") (pintype "passive"))
      (node (ref "C149") (pin "2") (pinfunction "2_2") (pintype "passive"))
      (node (ref "C152") (pin "1") (pinfunction "1_1") (pintype "passive"))
      (node (ref "C153") (pin "2") (pinfunction "2_2") (pintype "passive"))
      (node (ref "C154") (pin "1") (pinfunction "1_1") (pintype "passive"))
      (node (ref "C156") (pin "1") (pinfunction "1_1") (pintype "passive"))
      (node (ref "C157") (pin "2") (pinfunction "2_2") (pintype "passive"))
      (node (ref "C158") (pin "2") (pinfunction "2_2") (pintype "passive"))
      (node (ref "C159") (pin "2") (pinfunction "2_2") (pintype "passive"))
      (node (ref "IC30") (pin "1") (pinfunction "GND_1") (pintype "passive"))
      (node (ref "IC30") (pin "11") (pinfunction "GND_11") (pintype "passive"))
      (node (ref "IC30") (pin "12") (pinfunction "GND_12") (pintype "passive"))
      (node (ref "IC30") (pin "16") (pinfunction "GND_16") (pintype "passive"))
      (node (ref "IC30") (pin "19") (pinfunction "GND_19") (pintype "passive"))
      (node (ref "IC30") (pin "22") (pinfunction "SEL_22") (pintype "passive"))
      (node (ref "IC30") (pin "25") (pinfunction "GND_25") (pintype "passive"))
      (node (ref "IC30") (pin "7") (pinfunction "GND_7") (pintype "passive"))
      (node (ref "IC31") (pin "2") (pinfunction "GND_2") (pintype "passive"))
      (node (ref "IC32") (pin "2") (pinfunction "GND_2") (pintype "passive"))
      (node (ref "IC33") (pin "8") (pinfunction "GND_8") (pintype "passive"))
      (node (ref "IC34") (pin "1") (pinfunction "CPGND_1") (pintype "passive"))
      (node (ref "IC34") (pin "10") (pinfunction "DGND_10") (pintype "passive"))
      (node (ref "IC34") (pin "2") (pinfunction "AGND_2") (pintype "passive"))
      (node (ref "IC34") (pin "21") (pinfunction "AGND_21") (pintype "passive"))
      (node (ref "IC34") (pin "3") (pinfunction "AGND_3") (pintype "passive"))
      (node (ref "IC34") (pin "9") (pinfunction "DGND_9") (pintype "passive"))
      (node (ref "IC35") (pin "5") (pinfunction "GND_5") (pintype "power_in"))
      (node (ref "J33") (pin "2") (pinfunction "Y_2") (pintype "passive"))
      (node (ref "R168") (pin "1") (pinfunction "1_1") (pintype "passive"))
      (node (ref "R182") (pin "1") (pinfunction "1_1") (pintype "passive"))
      (node (ref "R189") (pin "1") (pinfunction "1_1") (pintype "passive"))
      (node (ref "R190") (pin "2") (pinfunction "2_2") (pintype "passive"))
      (node (ref "R191") (pin "2") (pinfunction "2_2") (pintype "passive"))
      (node (ref "R192") (pin "2") (pinfunction "2_2") (pintype "passive"))
      (node (ref "R193") (pin "1") (pinfunction "1_1") (pintype "passive"))
      (node (ref "R199") (pin "2") (pinfunction "2_2") (pintype "passive"))
      (node (ref "XO1") (pin "2") (pinfunction "GND_2") (pintype "passive"))
      (node (ref "XO2") (pin "2") (pinfunction "GND_2") (pintype "passive"))
      (node (ref "XO3") (pin "2") (pinfunction "GND_2") (pintype "passive"))
      (node (ref "XO4") (pin "4") (pinfunction "GND_4") (pintype "passive"))
      (node (ref "XO5") (pin "2") (pinfunction "GND_2") (pintype "passive"))
    )
    (net (code "24") (name "Net-(C112-Pad2)") (class "Default")
      (node (ref "C112") (pin "2") (pinfunction "2_2") (pintype "passive"))
      (node (ref "C113") (pin "1") (pinfunction "1_1") (pintype "passive"))
      (node (ref "R168") (pin "2") (pinfunction "2_2") (pintype "passive"))
    )
    (net (code "25") (name "Net-(C113-Pad2)") (class "Default")
      (node (ref "C113") (pin "2") (pinfunction "2_2") (pintype "passive"))
      (node (ref "R164") (pin "1") (pinfunction "1_1") (pintype "passive"))
      (node (ref "R170") (pin "1") (pinfunction "1_1") (pintype "passive"))
      (node (ref "R173") (pin "2") (pinfunction "2_2") (pintype "passive"))
      (node (ref "R176") (pin "1") (pinfunction "1_1") (pintype "passive"))
    )
    (net (code "26") (name "Net-(C135-Pad2)") (class "Default")
      (node (ref "C135") (pin "2") (pinfunction "2_2") (pintype "passive"))
      (node (ref "C136") (pin "1") (pinfunction "1_1") (pintype "passive"))
      (node (ref "C137") (pin "1") (pinfunction "1_1") (pintype "passive"))
      (node (ref "FR7") (pin "2") (pinfunction "2_2") (pintype "passive"))
      (node (ref "IC34") (pin "6") (pinfunction "AVdd_6") (pintype "passive"))
      (node (ref "IC34") (pin "7") (pinfunction "AVdd_7") (pintype "passive"))
    )
    (net (code "27") (name "Net-(C138-Pad2)") (class "Default")
      (node (ref "C138") (pin "2") (pinfunction "2_2") (pintype "passive"))
      (node (ref "C139") (pin "1") (pinfunction "1_1") (pintype "passive"))
      (node (ref "R182") (pin "2") (pinfunction "2_2") (pintype "passive"))
    )
    (net (code "28") (name "Net-(C143-Pad2)") (class "Default")
      (node (ref "C143") (pin "2") (pinfunction "2_2") (pintype "passive"))
      (node (ref "R180") (pin "1") (pinfunction "1_1") (pintype "passive"))
      (node (ref "R181") (pin "2") (pinfunction "2_2") (pintype "passive"))
      (node (ref "R194") (pin "2") (pinfunction "2_2") (pintype "passive"))
      (node (ref "R196") (pin "1") (pinfunction "1_1") (pintype "passive"))
      (node (ref "R199") (pin "1") (pinfunction "1_1") (pintype "passive"))
    )
    (net (code "29") (name "Net-(C150-Pad2)") (class "Default")
      (node (ref "C150") (pin "2") (pinfunction "2_2") (pintype "passive"))
      (node (ref "C151") (pin "1") (pinfunction "1_1") (pintype "passive"))
      (node (ref "R189") (pin "2") (pinfunction "2_2") (pintype "passive"))
    )
    (net (code "30") (name "Net-(C154-Pad2)") (class "Default")
      (node (ref "C154") (pin "2") (pinfunction "2_2") (pintype "passive"))
      (node (ref "R186") (pin "1") (pinfunction "1_1") (pintype "passive"))
      (node (ref "R188") (pin "2") (pinfunction "2_2") (pintype "passive"))
    )
    (net (code "31") (name "Net-(C155-Pad1)") (class "Default")
      (node (ref "C155") (pin "1") (pinfunction "1_1") (pintype "passive"))
      (node (ref "R193") (pin "2") (pinfunction "2_2") (pintype "passive"))
    )
    (net (code "32") (name "Net-(FR4-Pad2)") (class "Default")
      (node (ref "FR4") (pin "2") (pinfunction "2_2") (pintype "passive"))
      (node (ref "R165") (pin "1") (pinfunction "1_1") (pintype "passive"))
      (node (ref "R171") (pin "2") (pinfunction "2_2") (pintype "passive"))
      (node (ref "R172") (pin "1") (pinfunction "1_1") (pintype "passive"))
      (node (ref "R175") (pin "1") (pinfunction "1_1") (pintype "passive"))
    )
    (net (code "33") (name "Net-(IC30-CLKin)") (class "Default")
      (node (ref "C112") (pin "1") (pinfunction "1_1") (pintype "passive"))
      (node (ref "IC30") (pin "21") (pinfunction "CLKin_21") (pintype "passive"))
    )
    (net (code "34") (name "Net-(IC30-CLKin*)") (class "Default")
      (node (ref "C114") (pin "2") (pinfunction "2_2") (pintype "passive"))
      (node (ref "IC30") (pin "20") (pinfunction "CLKin*_20") (pintype "passive"))
    )
    (net (code "35") (name "Net-(IC30-OE)") (class "Default")
      (node (ref "IC30") (pin "24") (pinfunction "OE_24") (pintype "passive"))
      (node (ref "R166") (pin "1") (pinfunction "1_1") (pintype "passive"))
    )
    (net (code "36") (name "Net-(IC31-EN)") (class "Default")
      (node (ref "C130") (pin "2") (pinfunction "2_2") (pintype "passive"))
      (node (ref "C132") (pin "2") (pinfunction "2_2") (pintype "passive"))
      (node (ref "IC31") (pin "1") (pinfunction "IN_1") (pintype "input"))
      (node (ref "IC31") (pin "3") (pinfunction "EN_3") (pintype "input"))
      (node (ref "R175") (pin "2") (pinfunction "2_2") (pintype "passive"))
      (node (ref "R177") (pin "2") (pinfunction "2_2") (pintype "passive"))
    )
    (net (code "37") (name "Net-(IC31-OUT)") (class "Default")
      (node (ref "C131") (pin "2") (pinfunction "2_2") (pintype "passive"))
      (node (ref "C133") (pin "2") (pinfunction "2_2") (pintype "passive"))
      (node (ref "IC31") (pin "5") (pinfunction "OUT_5") (pintype "output"))
      (node (ref "R177") (pin "1") (pinfunction "1_1") (pintype "passive"))
      (node (ref "XO5") (pin "4") (pinfunction "VCC_4") (pintype "passive"))
    )
    (net (code "38") (name "Net-(IC33-Vdd)") (class "Default")
      (node (ref "C140") (pin "2") (pinfunction "2_2") (pintype "passive"))
      (node (ref "C141") (pin "1") (pinfunction "1_1") (pintype "passive"))
      (node (ref "C142") (pin "1") (pinfunction "1_1") (pintype "passive"))
      (node (ref "C159") (pin "1") (pinfunction "1_1") (pintype "passive"))
      (node (ref "FR8") (pin "1") (pinfunction "1_1") (pintype "passive"))
      (node (ref "IC33") (pin "1") (pinfunction "Vdd_1") (pintype "power_in"))
      (node (ref "IC35") (pin "4") (pinfunction "VDD_4") (pintype "power_in"))
      (node (ref "R185") (pin "2") (pinfunction "2_2") (pintype "passive"))
    )
    (net (code "39") (name "Net-(IC33-Vfb)") (class "Default")
      (node (ref "C148") (pin "1") (pinfunction "1_1") (pintype "passive"))
      (node (ref "IC33") (pin "3") (pinfunction "Vfb_3") (pintype "input"))
      (node (ref "IC33") (pin "4") (pinfunction "Vout_4") (pintype "output"))
      (node (ref "R180") (pin "2") (pinfunction "2_2") (pintype "passive"))
    )
    (net (code "40") (name "Net-(IC34-CE)") (class "Default")
      (node (ref "IC34") (pin "11") (pinfunction "CE_11") (pintype "passive"))
      (node (ref "R187") (pin "1") (pinfunction "1_1") (pintype "passive"))
    )
    (net (code "41") (name "Net-(IC34-CLK)") (class "Default")
      (node (ref "C158") (pin "1") (pinfunction "1_1") (pintype "passive"))
      (node (ref "IC34") (pin "12") (pinfunction "CLK_12") (pintype "passive"))
      (node (ref "R195") (pin "2") (pinfunction "2_2") (pintype "passive"))
    )
    (net (code "42") (name "Net-(IC34-CP)") (class "Default")
      (node (ref "C155") (pin "2") (pinfunction "2_2") (pintype "passive"))
      (node (ref "C156") (pin "2") (pinfunction "2_2") (pintype "passive"))
      (node (ref "IC34") (pin "20") (pinfunction "CP_20") (pintype "passive"))
      (node (ref "R188") (pin "1") (pinfunction "1_1") (pintype "passive"))
    )
    (net (code "43") (name "Net-(IC34-DATA)") (class "Default")
      (node (ref "IC34") (pin "13") (pinfunction "DATA_13") (pintype "passive"))
      (node (ref "R197") (pin "2") (pinfunction "2_2") (pintype "passive"))
    )
    (net (code "44") (name "Net-(IC34-LE)") (class "Default")
      (node (ref "IC34") (pin "14") (pinfunction "LE_14") (pintype "passive"))
      (node (ref "R198") (pin "2") (pinfunction "2_2") (pintype "passive"))
    )
    (net (code "45") (name "Net-(IC34-REFin)") (class "Default")
      (node (ref "C150") (pin "1") (pinfunction "1_1") (pintype "passive"))
      (node (ref "IC34") (pin "8") (pinfunction "REFin_8") (pintype "passive"))
    )
    (net (code "46") (name "Net-(IC34-RFinA)") (class "Default")
      (node (ref "C138") (pin "1") (pinfunction "1_1") (pintype "passive"))
      (node (ref "IC34") (pin "5") (pinfunction "RFinA_5") (pintype "passive"))
    )
    (net (code "47") (name "Net-(IC34-RFinB)") (class "Default")
      (node (ref "C157") (pin "1") (pinfunction "1_1") (pintype "passive"))
      (node (ref "IC34") (pin "4") (pinfunction "RFinB_4") (pintype "passive"))
    )
    (net (code "48") (name "Net-(IC34-Rset)") (class "Default")
      (node (ref "IC34") (pin "19") (pinfunction "Rset_19") (pintype "passive"))
      (node (ref "R192") (pin "1") (pinfunction "1_1") (pintype "passive"))
    )
    (net (code "49") (name "Net-(IC34-Vp)") (class "Default")
      (node (ref "C146") (pin "2") (pinfunction "2_2") (pintype "passive"))
      (node (ref "C149") (pin "1") (pinfunction "1_1") (pintype "passive"))
      (node (ref "IC34") (pin "18") (pinfunction "Vp_18") (pintype "passive"))
      (node (ref "R183") (pin "1") (pinfunction "1_1") (pintype "passive"))
    )
    (net (code "50") (name "Net-(IC35-VOUT)") (class "Default")
      (node (ref "IC35") (pin "6") (pinfunction "VOUT_6") (pintype "tri_state"))
      (node (ref "R196") (pin "2") (pinfunction "2_2") (pintype "passive"))
    )
    (net (code "51") (name "Net-(J33-X)") (class "Default")
      (node (ref "J33") (pin "1") (pinfunction "X_1") (pintype "passive"))
      (node (ref "R167") (pin "1") (pinfunction "1_1") (pintype "passive"))
    )
    (net (code "52") (name "Net-(R172-Pad2)") (class "Default")
      (node (ref "R172") (pin "2") (pinfunction "2_2") (pintype "passive"))
      (node (ref "R174") (pin "1") (pinfunction "1_1") (pintype "passive"))
    )
    (net (code "53") (name "Net-(XO1-Output)") (class "Default")
      (node (ref "R164") (pin "2") (pinfunction "2_2") (pintype "passive"))
      (node (ref "XO1") (pin "3") (pinfunction "Output_3") (pintype "output"))
    )
    (net (code "54") (name "Net-(XO1-Vcc)") (class "Default")
      (node (ref "C109") (pin "2") (pinfunction "2_2") (pintype "passive"))
      (node (ref "C110") (pin "2") (pinfunction "2_2") (pintype "passive"))
      (node (ref "C111") (pin "1") (pinfunction "1_1") (pintype "passive"))
      (node (ref "R165") (pin "2") (pinfunction "2_2") (pintype "passive"))
      (node (ref "XO1") (pin "4") (pinfunction "Vcc_4") (pintype "power_in"))
    )
    (net (code "55") (name "Net-(XO2-OUT)") (class "Default")
      (node (ref "R170") (pin "2") (pinfunction "2_2") (pintype "passive"))
      (node (ref "XO2") (pin "4") (pinfunction "OUT_4") (pintype "passive"))
      (node (ref "XO3") (pin "3") (pinfunction "OUT_3") (pintype "passive"))
    )
    (net (code "56") (name "Net-(XO2-TRI-ST.)") (class "Default")
      (node (ref "R169") (pin "1") (pinfunction "1_1") (pintype "passive"))
      (node (ref "XO2") (pin "6") (pinfunction "TRI-ST._6") (pintype "passive"))
    )
    (net (code "57") (name "Net-(XO2-VDD)") (class "Default")
      (node (ref "C115") (pin "2") (pinfunction "2_2") (pintype "passive"))
      (node (ref "C116") (pin "2") (pinfunction "2_2") (pintype "passive"))
      (node (ref "R169") (pin "2") (pinfunction "2_2") (pintype "passive"))
      (node (ref "R171") (pin "1") (pinfunction "1_1") (pintype "passive"))
      (node (ref "XO2") (pin "5") (pinfunction "VDD_5") (pintype "passive"))
      (node (ref "XO3") (pin "4") (pinfunction "VDD_4") (pintype "passive"))
    )
    (net (code "58") (name "Net-(XO4-RF_OUT)") (class "Default")
      (node (ref "R173") (pin "1") (pinfunction "1_1") (pintype "passive"))
      (node (ref "XO4") (pin "6") (pinfunction "RF_OUT_6") (pintype "output"))
    )
    (net (code "59") (name "Net-(XO4-VCC)") (class "Default")
      (node (ref "C121") (pin "2") (pinfunction "2_2") (pintype "passive"))
      (node (ref "C122") (pin "2") (pinfunction "2_2") (pintype "passive"))
      (node (ref "R174") (pin "2") (pinfunction "2_2") (pintype "passive"))
      (node (ref "XO4") (pin "9") (pinfunction "VCC_9") (pintype "power_in"))
    )
    (net (code "60") (name "Net-(XO4-VC_FILTER)") (class "Default")
      (node (ref "C123") (pin "2") (pinfunction "2_2") (pintype "passive"))
      (node (ref "XO4") (pin "7") (pinfunction "VC_FILTER_7") (pintype "input"))
    )
    (net (code "61") (name "Net-(XO5-OUT)") (class "Default")
      (node (ref "R176") (pin "2") (pinfunction "2_2") (pintype "passive"))
      (node (ref "R178") (pin "1") (pinfunction "1_1") (pintype "passive"))
      (node (ref "XO5") (pin "3") (pinfunction "OUT_3") (pintype "passive"))
    )
    (net (code "62") (name "VCC2P5_VREF") (class "Default")
      (node (ref "R184") (pin "2") (pinfunction "2_2") (pintype "passive"))
    )
    (net (code "63") (name "VCC3P3_CLK") (class "Default")
      (node (ref "C134") (pin "2") (pinfunction "2_2") (pintype "passive"))
      (node (ref "C144") (pin "1") (pinfunction "1_1") (pintype "passive"))
      (node (ref "C145") (pin "1") (pinfunction "1_1") (pintype "passive"))
      (node (ref "C147") (pin "2") (pinfunction "2_2") (pintype "passive"))
      (node (ref "FR4") (pin "1") (pinfunction "1_1") (pintype "passive"))
      (node (ref "FR5") (pin "1") (pinfunction "1_1") (pintype "passive"))
      (node (ref "FR6") (pin "1") (pinfunction "1_1") (pintype "passive"))
      (node (ref "FR7") (pin "1") (pinfunction "1_1") (pintype "passive"))
      (node (ref "FR8") (pin "2") (pinfunction "2_2") (pintype "passive"))
      (node (ref "IC32") (pin "5") (pinfunction "VCC_5") (pintype "passive"))
      (node (ref "IC34") (pin "16") (pinfunction "DVdd_16") (pintype "passive"))
      (node (ref "IC34") (pin "17") (pinfunction "DVdd_17") (pintype "passive"))
      (node (ref "R183") (pin "2") (pinfunction "2_2") (pintype "passive"))
      (node (ref "R187") (pin "2") (pinfunction "2_2") (pintype "passive"))
      (node (ref "R194") (pin "1") (pinfunction "1_1") (pintype "passive"))
    )
    (net (code "64") (name "VCC3P3_LMKRF") (class "Default")
      (node (ref "C117") (pin "2") (pinfunction "2_2") (pintype "passive"))
      (node (ref "C118") (pin "2") (pinfunction "2_2") (pintype "passive"))
      (node (ref "C119") (pin "2") (pinfunction "2_2") (pintype "passive"))
      (node (ref "C120") (pin "2") (pinfunction "2_2") (pintype "passive"))
      (node (ref "FR5") (pin "2") (pinfunction "2_2") (pintype "passive"))
      (node (ref "IC30") (pin "23") (pinfunction "Vdd_23") (pintype "passive"))
      (node (ref "IC30") (pin "8") (pinfunction "Vdd_8") (pintype "passive"))
      (node (ref "R166") (pin "2") (pinfunction "2_2") (pintype "passive"))
    )
    (net (code "65") (name "VCC3P3_LMKRF_VDDO") (class "Default")
      (node (ref "C124") (pin "2") (pinfunction "2_2") (pintype "passive"))
      (node (ref "C125") (pin "2") (pinfunction "2_2") (pintype "passive"))
      (node (ref "C126") (pin "2") (pinfunction "2_2") (pintype "passive"))
      (node (ref "C127") (pin "2") (pinfunction "2_2") (pintype "passive"))
      (node (ref "C128") (pin "2") (pinfunction "2_2") (pintype "passive"))
      (node (ref "C129") (pin "2") (pinfunction "2_2") (pintype "passive"))
      (node (ref "FR6") (pin "2") (pinfunction "2_2") (pintype "passive"))
      (node (ref "IC30") (pin "14") (pinfunction "Vddo_14") (pintype "passive"))
      (node (ref "IC30") (pin "18") (pinfunction "Vddo_18") (pintype "passive"))
      (node (ref "IC30") (pin "2") (pinfunction "Vddo_2") (pintype "passive"))
      (node (ref "IC30") (pin "6") (pinfunction "Vddo_6") (pintype "passive"))
    )
    (net (code "66") (name "unconnected-(IC30-OSCin-Pad9)") (class "Default")
      (node (ref "IC30") (pin "9") (pinfunction "OSCin_9") (pintype "passive+no_connect"))
    )
    (net (code "67") (name "unconnected-(IC30-OSCout-Pad10)") (class "Default")
      (node (ref "IC30") (pin "10") (pinfunction "OSCout_10") (pintype "passive+no_connect"))
    )
    (net (code "68") (name "unconnected-(IC31-NC-Pad4)") (class "Default")
      (node (ref "IC31") (pin "4") (pinfunction "NC_4") (pintype "passive+no_connect"))
    )
    (net (code "69") (name "unconnected-(XO2-T.S.-Pad3)") (class "Default")
      (node (ref "XO2") (pin "3") (pinfunction "T.S._3") (pintype "passive+no_connect"))
    )
    (net (code "70") (name "unconnected-(XO4-NC-Pad2)") (class "Default")
      (node (ref "XO4") (pin "2") (pinfunction "NC_2") (pintype "passive+no_connect"))
    )
    (net (code "71") (name "unconnected-(XO4-NC-Pad3)") (class "Default")
      (node (ref "XO4") (pin "3") (pinfunction "NC_3") (pintype "passive+no_connect"))
    )
    (net (code "72") (name "unconnected-(XO4-NC-Pad5)") (class "Default")
      (node (ref "XO4") (pin "5") (pinfunction "NC_5") (pintype "passive+no_connect"))
    )
    (net (code "73") (name "unconnected-(XO4-NC-Pad8)") (class "Default")
      (node (ref "XO4") (pin "8") (pinfunction "NC_8") (pintype "passive+no_connect"))
    )
    (net (code "74") (name "unconnected-(XO4-NC-Pad10)") (class "Default")
      (node (ref "XO4") (pin "10") (pinfunction "NC_10") (pintype "passive+no_connect"))
    )
  )
)
